# AnchorBoard_SNS_Power.net
KiCad netlist of a schematic drawn in Altium Designer
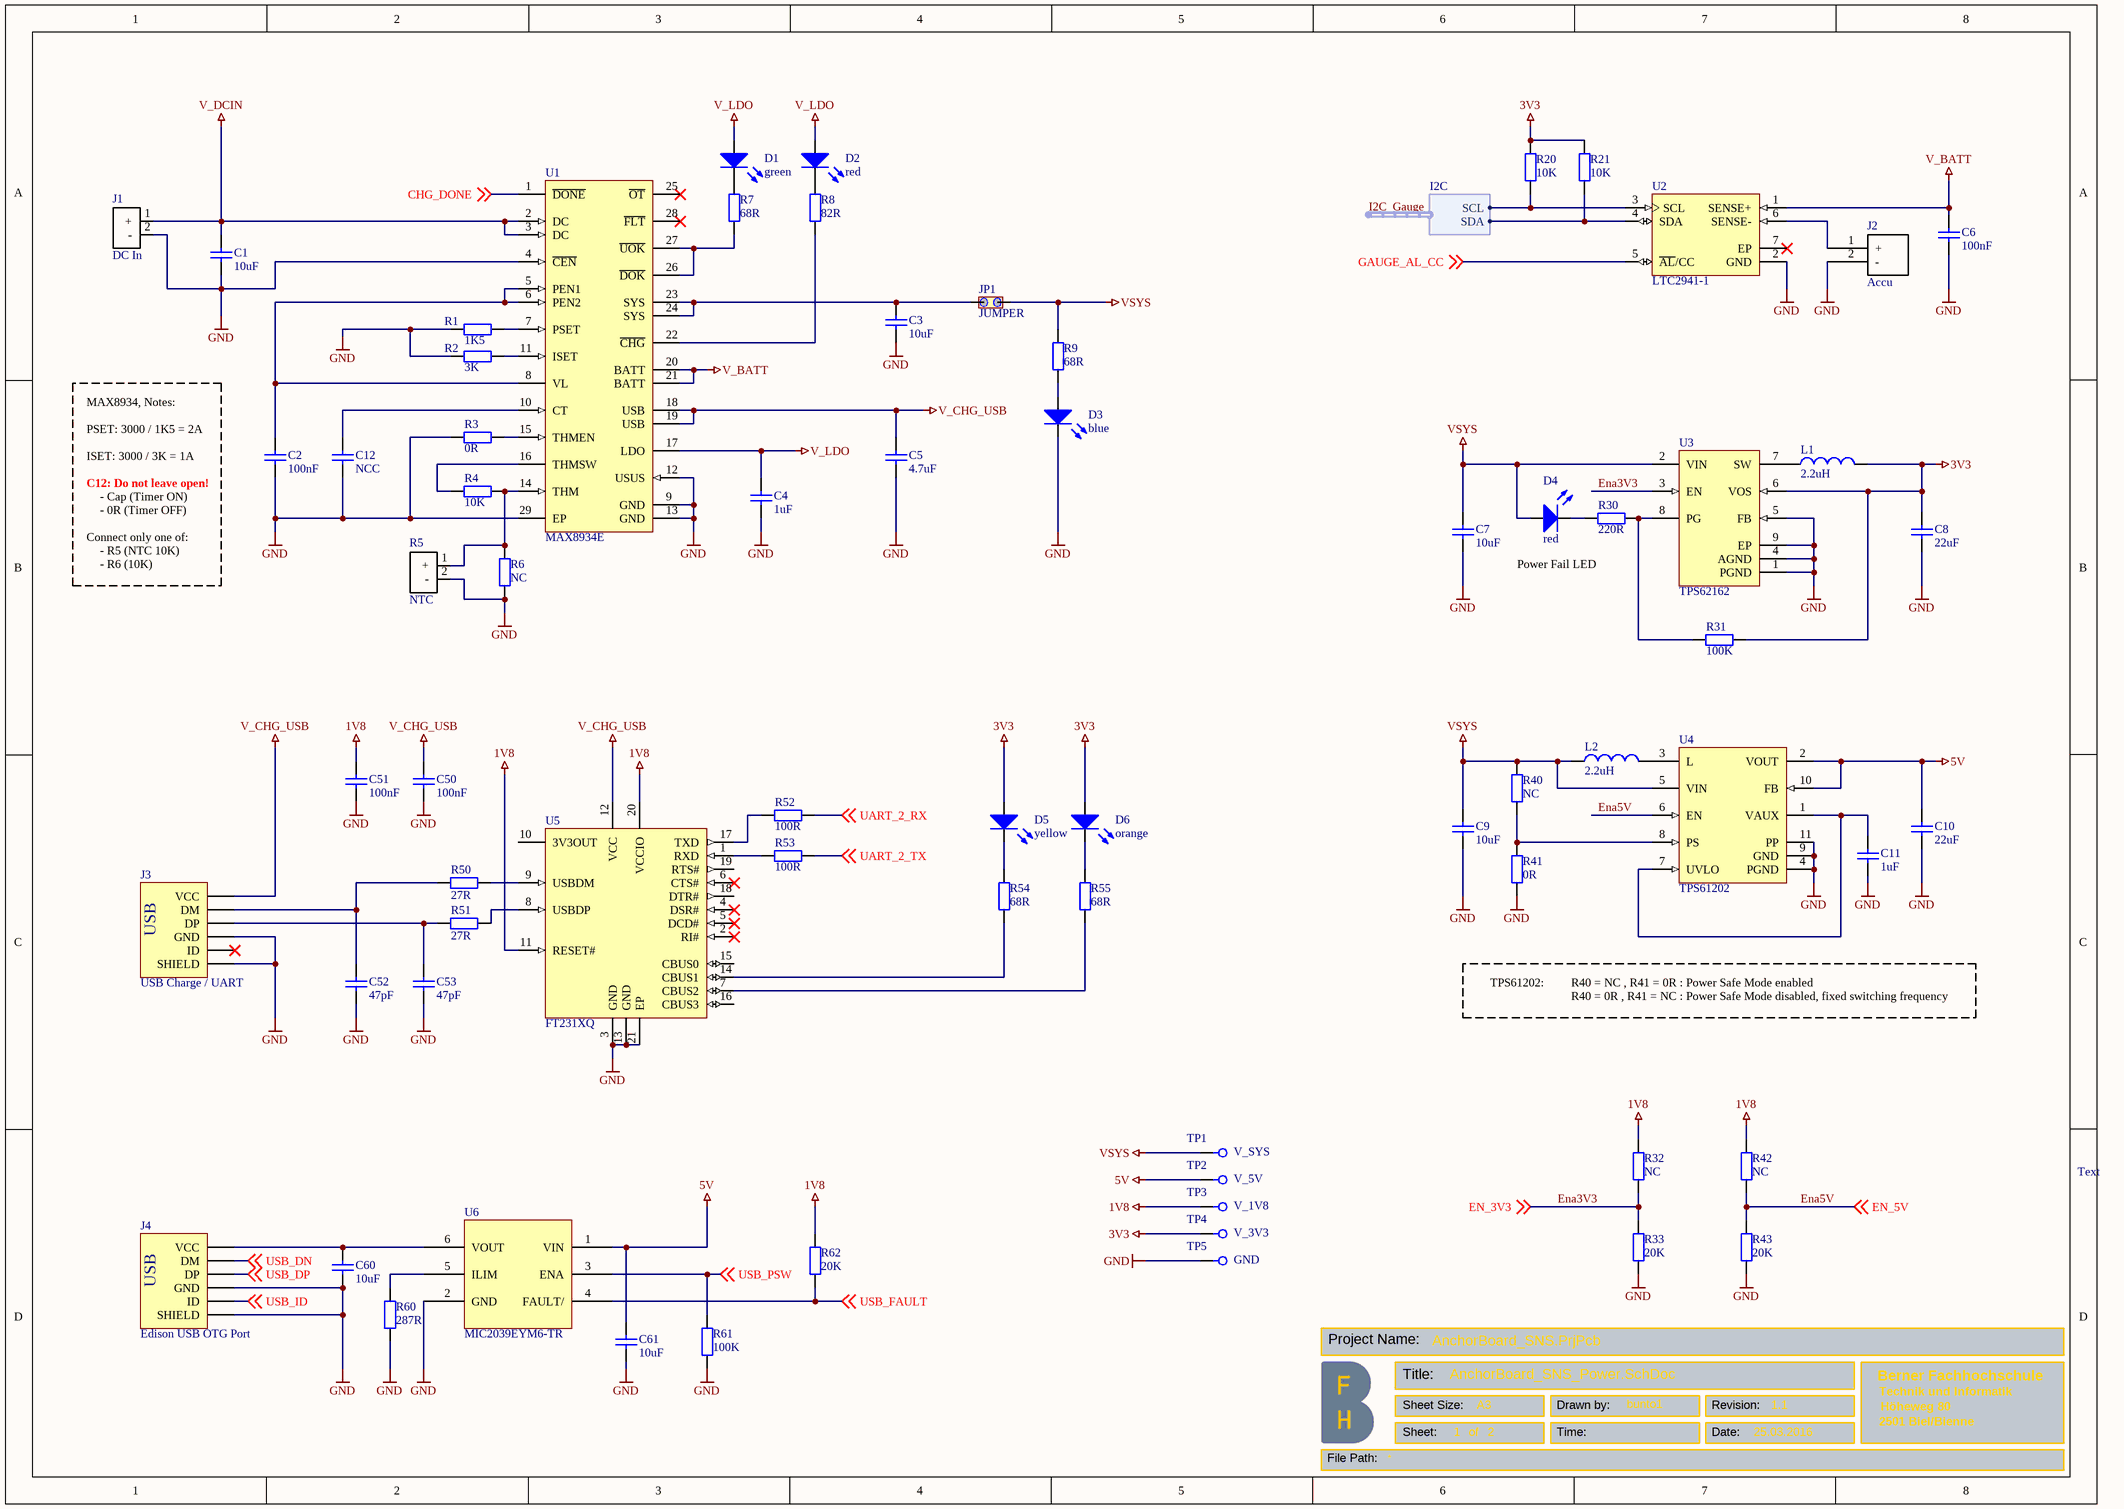
[diagram p0: AnchorBoard_SNS_Power.SchDoc]

(export (version "E")
  (design (tool "Eeschema 10.0.6"))
  (components
    (comp (ref "C1")
      (value "10uF")
      (footprint "CAPC1608X80")
      (description "Capacitor SMD Ceramic X7R")
      (libsource (lib "AnchorBoard_SNS") (part "Capacitor"))
    )
    (comp (ref "C2")
      (value "100nF")
      (footprint "CAPC1005X50")
      (description "Capacitor SMD")
      (libsource (lib "AnchorBoard_SNS") (part "Capacitor"))
    )
    (comp (ref "C3")
      (value "10uF")
      (footprint "CAPC1608X80")
      (description "Capacitor SMD Ceramic X7R")
      (libsource (lib "AnchorBoard_SNS") (part "Capacitor"))
    )
    (comp (ref "C4")
      (value "1uF")
      (footprint "CAPC1005X50")
      (description "Capacitor SMD Ceramic X7R Low ESR")
      (libsource (lib "AnchorBoard_SNS") (part "Capacitor"))
    )
    (comp (ref "C5")
      (value "4.7uF")
      (footprint "CAPC1608X80")
      (description "Capacitor SMD Ceramic X7R")
      (libsource (lib "AnchorBoard_SNS") (part "Capacitor"))
    )
    (comp (ref "C6")
      (value "100nF")
      (footprint "CAPC1005X50")
      (description "Capacitor SMD")
      (libsource (lib "AnchorBoard_SNS") (part "Capacitor"))
    )
    (comp (ref "C7")
      (value "10uF")
      (footprint "CAPC1608X80")
      (description "Capacitor SMD Ceramic X7R")
      (libsource (lib "AnchorBoard_SNS") (part "Capacitor"))
    )
    (comp (ref "C8")
      (value "22uF")
      (footprint "CAPC1608X80")
      (description "Capacitor SMD Ceramic X7R Low ESR")
      (libsource (lib "AnchorBoard_SNS") (part "Capacitor"))
    )
    (comp (ref "C9")
      (value "10uF")
      (footprint "CAPC1608X80")
      (description "Capacitor SMD Ceramic X7R")
      (libsource (lib "AnchorBoard_SNS") (part "Capacitor"))
    )
    (comp (ref "C10")
      (value "22uF")
      (footprint "CAPC1608X80")
      (description "Capacitor SMD Ceramic X7R Low ESR")
      (libsource (lib "AnchorBoard_SNS") (part "Capacitor"))
    )
    (comp (ref "C11")
      (value "1uF")
      (footprint "CAPC1005X50")
      (description "Capacitor SMD Ceramic X7R Low ESR")
      (libsource (lib "AnchorBoard_SNS") (part "Capacitor"))
    )
    (comp (ref "C12")
      (value "NCC")
      (footprint "RESC1005X35")
      (description "Capacitor SMD Ceramic X7R")
      (libsource (lib "AnchorBoard_SNS") (part "Capacitor"))
    )
    (comp (ref "C50")
      (value "100nF")
      (footprint "CAPC1005X50")
      (description "Capacitor SMD")
      (libsource (lib "AnchorBoard_SNS") (part "Capacitor"))
    )
    (comp (ref "C51")
      (value "100nF")
      (footprint "CAPC1005X50")
      (description "Capacitor SMD")
      (libsource (lib "AnchorBoard_SNS") (part "Capacitor"))
    )
    (comp (ref "C52")
      (value "47pF")
      (footprint "CAPC1005X50")
      (description "Capacitor SMD")
      (libsource (lib "AnchorBoard_SNS") (part "Capacitor"))
    )
    (comp (ref "C53")
      (value "47pF")
      (footprint "CAPC1005X50")
      (description "Capacitor SMD")
      (libsource (lib "AnchorBoard_SNS") (part "Capacitor"))
    )
    (comp (ref "C60")
      (value "10uF")
      (footprint "CAPC1608X80")
      (description "Capacitor SMD Ceramic X7R")
      (libsource (lib "AnchorBoard_SNS") (part "Capacitor"))
    )
    (comp (ref "C61")
      (value "10uF")
      (footprint "CAPC1608X80")
      (description "Capacitor SMD Ceramic X7R")
      (libsource (lib "AnchorBoard_SNS") (part "Capacitor"))
    )
    (comp (ref "D1")
      (value "green")
      (footprint "LEDM1608X80")
      (description "Light Emitting Diode")
      (fields (field (name "MANUFACTURER") "Lite-On") (field (name "MODIFIED_BY") "bunto1"))
      (libsource (lib "AnchorBoard_SNS") (part "LED_green"))
    )
    (comp (ref "D2")
      (value "red")
      (footprint "LEDM1608X80")
      (description "Light Emitting Diode")
      (fields (field (name "MANUFACTURER") "Lite-On") (field (name "MODIFIED_BY") "bunto1"))
      (libsource (lib "AnchorBoard_SNS") (part "LED_red"))
    )
    (comp (ref "D3")
      (value "blue")
      (footprint "LEDM1608X80")
      (description "Light Emitting Diode")
      (fields (field (name "MANUFACTURER") "Lite-On") (field (name "MODIFIED_BY") "bunto1"))
      (libsource (lib "AnchorBoard_SNS") (part "LED_blue"))
    )
    (comp (ref "D4")
      (value "red")
      (footprint "LEDM1608X80")
      (description "Light Emitting Diode")
      (fields (field (name "MANUFACTURER") "Lite-On") (field (name "MODIFIED_BY") "bunto1"))
      (libsource (lib "AnchorBoard_SNS") (part "LED_red"))
    )
    (comp (ref "D5")
      (value "yellow")
      (footprint "LEDM1608X80")
      (description "Light Emitting Diode")
      (fields (field (name "MANUFACTURER") "Lite-On") (field (name "MODIFIED_BY") "bunto1"))
      (libsource (lib "AnchorBoard_SNS") (part "LED_yellow"))
    )
    (comp (ref "D6")
      (value "orange")
      (footprint "LEDM1608X80")
      (description "Light Emitting Diode")
      (fields (field (name "MANUFACTURER") "Lite-On") (field (name "MODIFIED_BY") "bunto1"))
      (libsource (lib "AnchorBoard_SNS") (part "LED_orange"))
    )
    (comp (ref "J1")
      (value "DC In")
      (footprint "ACCU_PORT")
      (description "2-Pin THT Port")
      (libsource (lib "AnchorBoard_SNS") (part "PORT_THT"))
    )
    (comp (ref "J2")
      (value "Accu")
      (footprint "ACCU_PORT")
      (description "Accu Port")
      (libsource (lib "AnchorBoard_SNS") (part "ACCU_PORT"))
    )
    (comp (ref "J3")
      (value "USB Charge / UART")
      (footprint "MOLEX_0473460001")
      (description "USB Connectors MICRO USB B RECPT")
      (libsource (lib "AnchorBoard_SNS") (part "USB_micro_B"))
    )
    (comp (ref "J4")
      (value "Edison USB OTG Port")
      (footprint "MOLEX_0473460001")
      (description "USB Connectors MICRO USB B RECPT")
      (libsource (lib "AnchorBoard_SNS") (part "USB_micro_B"))
    )
    (comp (ref "JP1")
      (value "JUMPER")
      (footprint "HDR1X2_V_M")
      (description "Jumper")
      (libsource (lib "AnchorBoard_SNS") (part "JUMPER"))
    )
    (comp (ref "L1")
      (value "2.2uH")
      (footprint "INDM2929X140")
      (description "Inductor")
      (fields (field (name "MODIFIED_BY") "BEP"))
      (libsource (lib "AnchorBoard_SNS") (part "L"))
    )
    (comp (ref "L2")
      (value "2.2uH")
      (footprint "INDM2929X140")
      (description "Inductor")
      (fields (field (name "MODIFIED_BY") "BEP"))
      (libsource (lib "AnchorBoard_SNS") (part "L"))
    )
    (comp (ref "R1")
      (value "1K5")
      (footprint "RESC1005X35")
      (description "Resistor")
      (libsource (lib "") (part "Resistor_1"))
    )
    (comp (ref "R2")
      (value "3K")
      (footprint "RESC1005X35")
      (description "Resistor")
      (libsource (lib "") (part "Resistor_1"))
    )
    (comp (ref "R3")
      (value "0R")
      (footprint "RESC1005X35")
      (description "Resistor")
      (libsource (lib "") (part "Resistor_3"))
    )
    (comp (ref "R4")
      (value "10K")
      (footprint "RESC1005X35")
      (description "Resistor")
      (libsource (lib "") (part "Resistor_1"))
    )
    (comp (ref "R5")
      (value "NTC")
      (footprint "ACCU_PORT")
      (description "2-Pin THT Port")
      (libsource (lib "AnchorBoard_SNS") (part "PORT_THT"))
    )
    (comp (ref "R6")
      (value "NC")
      (footprint "RESC1005X35")
      (description "Resistor")
      (libsource (lib "AnchorBoard_SNS") (part "Resistor"))
    )
    (comp (ref "R7")
      (value "68R")
      (footprint "RESC1005X35")
      (description "Resistor")
      (libsource (lib "AnchorBoard_SNS") (part "Resistor"))
    )
    (comp (ref "R8")
      (value "82R")
      (footprint "RESC1005X35")
      (description "Resistor")
      (libsource (lib "") (part "Resistor_2"))
    )
    (comp (ref "R9")
      (value "68R")
      (footprint "RESC1005X35")
      (description "Resistor")
      (libsource (lib "AnchorBoard_SNS") (part "Resistor"))
    )
    (comp (ref "R20")
      (value "10K")
      (footprint "RESC1005X35")
      (description "Resistor")
      (libsource (lib "AnchorBoard_SNS") (part "Resistor"))
    )
    (comp (ref "R21")
      (value "10K")
      (footprint "RESC1005X35")
      (description "Resistor")
      (libsource (lib "AnchorBoard_SNS") (part "Resistor"))
    )
    (comp (ref "R30")
      (value "220R")
      (footprint "RESC1005X35")
      (description "Resistor")
      (libsource (lib "") (part "Resistor_3"))
    )
    (comp (ref "R31")
      (value "100K")
      (footprint "RESC1005X35")
      (description "Resistor")
      (libsource (lib "") (part "Resistor_3"))
    )
    (comp (ref "R32")
      (value "NC")
      (footprint "RESC1005X35")
      (description "Resistor")
      (libsource (lib "") (part "Resistor_2"))
    )
    (comp (ref "R33")
      (value "20K")
      (footprint "RESC1005X35")
      (description "Resistor")
      (libsource (lib "AnchorBoard_SNS") (part "Resistor"))
    )
    (comp (ref "R40")
      (value "NC")
      (footprint "RESC1005X35")
      (description "Resistor")
      (libsource (lib "") (part "Resistor_2"))
    )
    (comp (ref "R41")
      (value "0R")
      (footprint "RESC1005X35")
      (description "Resistor")
      (libsource (lib "") (part "Resistor_2"))
    )
    (comp (ref "R42")
      (value "NC")
      (footprint "RESC1005X35")
      (description "Resistor")
      (libsource (lib "") (part "Resistor_2"))
    )
    (comp (ref "R43")
      (value "20K")
      (footprint "RESC1005X35")
      (description "Resistor")
      (libsource (lib "AnchorBoard_SNS") (part "Resistor"))
    )
    (comp (ref "R50")
      (value "27R")
      (footprint "RESC1005X35")
      (description "Resistor")
      (libsource (lib "") (part "Resistor_3"))
    )
    (comp (ref "R51")
      (value "27R")
      (footprint "RESC1005X35")
      (description "Resistor")
      (libsource (lib "") (part "Resistor_3"))
    )
    (comp (ref "R52")
      (value "100R")
      (footprint "RESC1005X35")
      (description "Resistor")
      (libsource (lib "") (part "Resistor_1"))
    )
    (comp (ref "R53")
      (value "100R")
      (footprint "RESC1005X35")
      (description "Resistor")
      (libsource (lib "") (part "Resistor_1"))
    )
    (comp (ref "R54")
      (value "68R")
      (footprint "RESC1005X35")
      (description "Resistor")
      (libsource (lib "AnchorBoard_SNS") (part "Resistor"))
    )
    (comp (ref "R55")
      (value "68R")
      (footprint "RESC1005X35")
      (description "Resistor")
      (libsource (lib "") (part "Resistor_2"))
    )
    (comp (ref "R60")
      (value "287R")
      (footprint "RESC1005X35")
      (description "Resistor")
      (libsource (lib "AnchorBoard_SNS") (part "Resistor"))
    )
    (comp (ref "R61")
      (value "100K")
      (footprint "RESC1005X35")
      (description "Resistor")
      (libsource (lib "AnchorBoard_SNS") (part "Resistor"))
    )
    (comp (ref "R62")
      (value "20K")
      (footprint "RESC1005X35")
      (description "Resistor")
      (libsource (lib "AnchorBoard_SNS") (part "Resistor"))
    )
    (comp (ref "TP1")
      (value "V_SYS")
      (footprint "TP_THT")
      (description "Test-Point")
      (libsource (lib "AnchorBoard_SNS") (part "TP1"))
    )
    (comp (ref "TP2")
      (value "V_5V")
      (footprint "TP_THT")
      (description "Test-Point")
      (libsource (lib "AnchorBoard_SNS") (part "TP1"))
    )
    (comp (ref "TP3")
      (value "V_1V8")
      (footprint "TP_THT")
      (description "Test-Point")
      (libsource (lib "AnchorBoard_SNS") (part "TP1"))
    )
    (comp (ref "TP4")
      (value "V_3V3")
      (footprint "TP_THT")
      (description "Test-Point")
      (libsource (lib "AnchorBoard_SNS") (part "TP1"))
    )
    (comp (ref "TP5")
      (value "GND")
      (footprint "TP_THT")
      (description "Test-Point")
      (libsource (lib "AnchorBoard_SNS") (part "TP1"))
    )
    (comp (ref "U1")
      (value "MAX8934E")
      (footprint "QFN40P40X40X80-29")
      (description "IC BATTERY CHARGER DUAL 28TQFN")
      (libsource (lib "AnchorBoard_SNS") (part "MAX8934E"))
    )
    (comp (ref "U2")
      (value "LTC2941-1")
      (footprint "DFN30X20X80-6")
      (description "IC FUEL/GAS GAUGE LI-ION 1A 6DFN")
      (libsource (lib "AnchorBoard_SNS") (part "LTC2941-1"))
    )
    (comp (ref "U3")
      (value "TPS62162")
      (footprint "SON50P210X210X80-9")
      (description "IC REG BUCK 3.3V 1A SYNC 8WSON")
      (libsource (lib "AnchorBoard_SNS") (part "TPS62162"))
    )
    (comp (ref "U4")
      (value "TPS61202")
      (footprint "SON50P310X310X100-11")
      (description "IC REG BOOST 5V 1.2A SYNC 10SON")
      (libsource (lib "AnchorBoard_SNS") (part "TPS61202"))
    )
    (comp (ref "U5")
      (value "FT231XQ")
      (footprint "QFN50P40X40X80-21")
      (description "IC USB SERIAL FULL UART 20QFN")
      (libsource (lib "AnchorBoard_SNS") (part "FT231XQ"))
    )
    (comp (ref "U6")
      (value "MIC2039EYM6-TR")
      (footprint "SOT95P360X130-6")
      (description "Adjustable Current Limit Power Switch")
      (libsource (lib "AnchorBoard_SNS") (part "MIC2039"))
    )
  )
  (nets
    (net (code "3") (name "1V8") (class "Default")
      (node (ref "C51") (pin "2") (pinfunction "2_2") (pintype "passive"))
      (node (ref "R32") (pin "2") (pinfunction "2_2") (pintype "passive"))
      (node (ref "R42") (pin "2") (pinfunction "2_2") (pintype "passive"))
      (node (ref "R62") (pin "1") (pinfunction "1_1") (pintype "passive"))
      (node (ref "TP3") (pin "1") (pinfunction "TP_1") (pintype "passive"))
      (node (ref "U5") (pin "11") (pinfunction "RESET#_11") (pintype "input"))
      (node (ref "U5") (pin "20") (pinfunction "VCCIO_20") (pintype "power_in"))
    )
    (net (code "4") (name "3V3") (class "Default")
      (node (ref "C8") (pin "2") (pinfunction "2_2") (pintype "passive"))
      (node (ref "D5") (pin "1") (pinfunction "A_1") (pintype "passive"))
      (node (ref "D6") (pin "1") (pinfunction "A_1") (pintype "passive"))
      (node (ref "L1") (pin "2") (pintype "passive"))
      (node (ref "R20") (pin "1") (pinfunction "1_1") (pintype "passive"))
      (node (ref "R21") (pin "1") (pinfunction "1_1") (pintype "passive"))
      (node (ref "R31") (pin "2") (pinfunction "2_2") (pintype "passive"))
      (node (ref "TP4") (pin "1") (pinfunction "TP_1") (pintype "passive"))
      (node (ref "U3") (pin "6") (pinfunction "VOS_6") (pintype "input"))
    )
    (net (code "5") (name "5V") (class "Default")
      (node (ref "C10") (pin "2") (pinfunction "2_2") (pintype "passive"))
      (node (ref "C61") (pin "2") (pinfunction "2_2") (pintype "passive"))
      (node (ref "TP2") (pin "1") (pinfunction "TP_1") (pintype "passive"))
      (node (ref "U4") (pin "10") (pinfunction "FB_10") (pintype "input"))
      (node (ref "U4") (pin "2") (pinfunction "VOUT_2") (pintype "power_in"))
      (node (ref "U6") (pin "1") (pinfunction "VIN_1") (pintype "passive"))
    )
    (net (code "6") (name "CHG_DONE") (class "Default")
      (node (ref "U1") (pin "1") (pinfunction "~{DONE}_1") (pintype "passive"))
    )
    (net (code "7") (name "EN_3V3") (class "Default")
      (node (ref "R32") (pin "1") (pinfunction "1_1") (pintype "passive"))
      (node (ref "R33") (pin "1") (pinfunction "1_1") (pintype "passive"))
      (node (ref "U3") (pin "3") (pinfunction "EN_3") (pintype "input"))
    )
    (net (code "8") (name "EN_5V") (class "Default")
      (node (ref "R42") (pin "1") (pinfunction "1_1") (pintype "passive"))
      (node (ref "R43") (pin "1") (pinfunction "1_1") (pintype "passive"))
      (node (ref "U4") (pin "6") (pinfunction "EN_6") (pintype "input"))
    )
    (net (code "9") (name "GAUGE_AL_CC") (class "Default")
      (node (ref "U2") (pin "5") (pinfunction "~{AL}/CC_5") (pintype "bidirectional"))
    )
    (net (code "10") (name "GND") (class "Default")
      (node (ref "C1") (pin "1") (pinfunction "1_1") (pintype "passive"))
      (node (ref "C10") (pin "1") (pinfunction "1_1") (pintype "passive"))
      (node (ref "C11") (pin "1") (pinfunction "1_1") (pintype "passive"))
      (node (ref "C12") (pin "1") (pinfunction "1_1") (pintype "passive"))
      (node (ref "C2") (pin "1") (pinfunction "1_1") (pintype "passive"))
      (node (ref "C3") (pin "1") (pinfunction "1_1") (pintype "passive"))
      (node (ref "C4") (pin "1") (pinfunction "1_1") (pintype "passive"))
      (node (ref "C5") (pin "1") (pinfunction "1_1") (pintype "passive"))
      (node (ref "C50") (pin "1") (pinfunction "1_1") (pintype "passive"))
      (node (ref "C51") (pin "1") (pinfunction "1_1") (pintype "passive"))
      (node (ref "C52") (pin "1") (pinfunction "1_1") (pintype "passive"))
      (node (ref "C53") (pin "1") (pinfunction "1_1") (pintype "passive"))
      (node (ref "C6") (pin "1") (pinfunction "1_1") (pintype "passive"))
      (node (ref "C60") (pin "1") (pinfunction "1_1") (pintype "passive"))
      (node (ref "C61") (pin "1") (pinfunction "1_1") (pintype "passive"))
      (node (ref "C7") (pin "1") (pinfunction "1_1") (pintype "passive"))
      (node (ref "C8") (pin "1") (pinfunction "1_1") (pintype "passive"))
      (node (ref "C9") (pin "1") (pinfunction "1_1") (pintype "passive"))
      (node (ref "D3") (pin "2") (pinfunction "K_2") (pintype "passive"))
      (node (ref "J1") (pin "2") (pinfunction "-_2") (pintype "passive"))
      (node (ref "J2") (pin "2") (pinfunction "-_2") (pintype "passive"))
      (node (ref "J3") (pin "5") (pinfunction "GND_5") (pintype "passive"))
      (node (ref "J3") (pin "6") (pinfunction "SHIELD_6") (pintype "passive"))
      (node (ref "J4") (pin "5") (pinfunction "GND_5") (pintype "passive"))
      (node (ref "J4") (pin "6") (pinfunction "SHIELD_6") (pintype "passive"))
      (node (ref "R1") (pin "2") (pinfunction "2_2") (pintype "passive"))
      (node (ref "R2") (pin "2") (pinfunction "2_2") (pintype "passive"))
      (node (ref "R3") (pin "1") (pinfunction "1_1") (pintype "passive"))
      (node (ref "R33") (pin "2") (pinfunction "2_2") (pintype "passive"))
      (node (ref "R41") (pin "1") (pinfunction "1_1") (pintype "passive"))
      (node (ref "R43") (pin "2") (pinfunction "2_2") (pintype "passive"))
      (node (ref "R5") (pin "2") (pinfunction "-_2") (pintype "passive"))
      (node (ref "R6") (pin "2") (pinfunction "2_2") (pintype "passive"))
      (node (ref "R60") (pin "2") (pinfunction "2_2") (pintype "passive"))
      (node (ref "R61") (pin "2") (pinfunction "2_2") (pintype "passive"))
      (node (ref "TP5") (pin "1") (pinfunction "TP_1") (pintype "passive"))
      (node (ref "U1") (pin "12") (pinfunction "USUS_12") (pintype "input"))
      (node (ref "U1") (pin "13") (pinfunction "GND_13") (pintype "power_in"))
      (node (ref "U1") (pin "29") (pinfunction "EP_29") (pintype "power_in"))
      (node (ref "U1") (pin "4") (pinfunction "~{CEN}_4") (pintype "input"))
      (node (ref "U1") (pin "9") (pinfunction "GND_9") (pintype "power_in"))
      (node (ref "U2") (pin "2") (pinfunction "GND_2") (pintype "power_in"))
      (node (ref "U3") (pin "1") (pinfunction "PGND_1") (pintype "power_in"))
      (node (ref "U3") (pin "4") (pinfunction "AGND_4") (pintype "power_in"))
      (node (ref "U3") (pin "5") (pinfunction "FB_5") (pintype "input"))
      (node (ref "U3") (pin "9") (pinfunction "EP_9") (pintype "power_in"))
      (node (ref "U4") (pin "11") (pinfunction "PP_11") (pintype "power_in"))
      (node (ref "U4") (pin "4") (pinfunction "PGND_4") (pintype "power_in"))
      (node (ref "U4") (pin "9") (pinfunction "GND_9") (pintype "power_in"))
      (node (ref "U5") (pin "13") (pinfunction "GND_13") (pintype "power_in"))
      (node (ref "U5") (pin "21") (pinfunction "EP_21") (pintype "power_in"))
      (node (ref "U5") (pin "3") (pinfunction "GND_3") (pintype "power_in"))
      (node (ref "U6") (pin "2") (pinfunction "GND_2") (pintype "passive"))
    )
    (net (code "11") (name "Net-(C3-Pad2)") (class "Default")
      (node (ref "C3") (pin "2") (pinfunction "2_2") (pintype "passive"))
      (node (ref "JP1") (pin "1") (pintype "passive"))
      (node (ref "U1") (pin "23") (pinfunction "SYS_23") (pintype "power_in"))
      (node (ref "U1") (pin "24") (pinfunction "SYS_24") (pintype "power_in"))
    )
    (net (code "12") (name "Net-(D1-K)") (class "Default")
      (node (ref "D1") (pin "2") (pinfunction "K_2") (pintype "passive"))
      (node (ref "R7") (pin "1") (pinfunction "1_1") (pintype "passive"))
    )
    (net (code "13") (name "Net-(D2-K)") (class "Default")
      (node (ref "D2") (pin "2") (pinfunction "K_2") (pintype "passive"))
      (node (ref "R8") (pin "2") (pinfunction "2_2") (pintype "passive"))
    )
    (net (code "14") (name "Net-(D3-A)") (class "Default")
      (node (ref "D3") (pin "1") (pinfunction "A_1") (pintype "passive"))
      (node (ref "R9") (pin "2") (pinfunction "2_2") (pintype "passive"))
    )
    (net (code "15") (name "Net-(D4-K)") (class "Default")
      (node (ref "D4") (pin "2") (pinfunction "K_2") (pintype "passive"))
      (node (ref "R30") (pin "1") (pinfunction "1_1") (pintype "passive"))
    )
    (net (code "16") (name "Net-(D5-K)") (class "Default")
      (node (ref "D5") (pin "2") (pinfunction "K_2") (pintype "passive"))
      (node (ref "R54") (pin "1") (pinfunction "1_1") (pintype "passive"))
    )
    (net (code "17") (name "Net-(D6-K)") (class "Default")
      (node (ref "D6") (pin "2") (pinfunction "K_2") (pintype "passive"))
      (node (ref "R55") (pin "2") (pinfunction "2_2") (pintype "passive"))
    )
    (net (code "18") (name "Net-(J2-+)") (class "Default")
      (node (ref "J2") (pin "1") (pinfunction "+_1") (pintype "passive"))
      (node (ref "U2") (pin "6") (pinfunction "SENSE-_6") (pintype "input"))
    )
    (net (code "19") (name "Net-(J3-DM)") (class "Default")
      (node (ref "C52") (pin "2") (pinfunction "2_2") (pintype "passive"))
      (node (ref "J3") (pin "2") (pinfunction "DM_2") (pintype "passive"))
      (node (ref "R50") (pin "1") (pinfunction "1_1") (pintype "passive"))
    )
    (net (code "20") (name "Net-(J3-DP)") (class "Default")
      (node (ref "C53") (pin "2") (pinfunction "2_2") (pintype "passive"))
      (node (ref "J3") (pin "3") (pinfunction "DP_3") (pintype "passive"))
      (node (ref "R51") (pin "1") (pinfunction "1_1") (pintype "passive"))
    )
    (net (code "21") (name "Net-(J4-VCC)") (class "Default")
      (node (ref "C60") (pin "2") (pinfunction "2_2") (pintype "passive"))
      (node (ref "J4") (pin "1") (pinfunction "VCC_1") (pintype "passive"))
      (node (ref "U6") (pin "6") (pinfunction "VOUT_6") (pintype "passive"))
    )
    (net (code "22") (name "Net-(R5-+)") (class "Default")
      (node (ref "R4") (pin "1") (pinfunction "1_1") (pintype "passive"))
      (node (ref "R5") (pin "1") (pinfunction "+_1") (pintype "passive"))
      (node (ref "R6") (pin "1") (pinfunction "1_1") (pintype "passive"))
      (node (ref "U1") (pin "14") (pinfunction "THM_14") (pintype "input"))
    )
    (net (code "23") (name "Net-(U1-CT)") (class "Default")
      (node (ref "C12") (pin "2") (pinfunction "2_2") (pintype "passive"))
      (node (ref "U1") (pin "10") (pinfunction "CT_10") (pintype "input"))
    )
    (net (code "24") (name "Net-(U1-ISET)") (class "Default")
      (node (ref "R2") (pin "1") (pinfunction "1_1") (pintype "passive"))
      (node (ref "U1") (pin "11") (pinfunction "ISET_11") (pintype "input"))
    )
    (net (code "25") (name "Net-(U1-PEN1)") (class "Default")
      (node (ref "C2") (pin "2") (pinfunction "2_2") (pintype "passive"))
      (node (ref "U1") (pin "5") (pinfunction "PEN1_5") (pintype "input"))
      (node (ref "U1") (pin "6") (pinfunction "PEN2_6") (pintype "input"))
      (node (ref "U1") (pin "8") (pinfunction "VL_8") (pintype "power_in"))
    )
    (net (code "26") (name "Net-(U1-PSET)") (class "Default")
      (node (ref "R1") (pin "1") (pinfunction "1_1") (pintype "passive"))
      (node (ref "U1") (pin "7") (pinfunction "PSET_7") (pintype "input"))
    )
    (net (code "27") (name "Net-(U1-THMEN)") (class "Default")
      (node (ref "R3") (pin "2") (pinfunction "2_2") (pintype "passive"))
      (node (ref "U1") (pin "15") (pinfunction "THMEN_15") (pintype "input"))
    )
    (net (code "28") (name "Net-(U1-THMSW)") (class "Default")
      (node (ref "R4") (pin "2") (pinfunction "2_2") (pintype "passive"))
      (node (ref "U1") (pin "16") (pinfunction "THMSW_16") (pintype "passive"))
    )
    (net (code "29") (name "Net-(U1-~{CHG})") (class "Default")
      (node (ref "R8") (pin "1") (pinfunction "1_1") (pintype "passive"))
      (node (ref "U1") (pin "22") (pinfunction "~{CHG}_22") (pintype "passive"))
    )
    (net (code "30") (name "Net-(U1-~{DOK})") (class "Default")
      (node (ref "R7") (pin "2") (pinfunction "2_2") (pintype "passive"))
      (node (ref "U1") (pin "26") (pinfunction "~{DOK}_26") (pintype "open_collector"))
      (node (ref "U1") (pin "27") (pinfunction "~{UOK}_27") (pintype "open_collector"))
    )
    (net (code "31") (name "Net-(U2-SCL)") (class "Default")
      (node (ref "R20") (pin "2") (pinfunction "2_2") (pintype "passive"))
      (node (ref "U2") (pin "3") (pinfunction "SCL_3") (pintype "input"))
    )
    (net (code "32") (name "Net-(U2-SDA)") (class "Default")
      (node (ref "R21") (pin "2") (pinfunction "2_2") (pintype "passive"))
      (node (ref "U2") (pin "4") (pinfunction "SDA_4") (pintype "bidirectional"))
    )
    (net (code "33") (name "Net-(U3-PG)") (class "Default")
      (node (ref "R30") (pin "2") (pinfunction "2_2") (pintype "passive"))
      (node (ref "R31") (pin "1") (pinfunction "1_1") (pintype "passive"))
      (node (ref "U3") (pin "8") (pinfunction "PG_8") (pintype "tri_state"))
    )
    (net (code "34") (name "Net-(U3-SW)") (class "Default")
      (node (ref "L1") (pin "1") (pintype "passive"))
      (node (ref "U3") (pin "7") (pinfunction "SW_7") (pintype "power_in"))
    )
    (net (code "35") (name "Net-(U4-L)") (class "Default")
      (node (ref "L2") (pin "2") (pintype "passive"))
      (node (ref "U4") (pin "3") (pinfunction "L_3") (pintype "power_in"))
    )
    (net (code "36") (name "Net-(U4-PS)") (class "Default")
      (node (ref "R40") (pin "1") (pinfunction "1_1") (pintype "passive"))
      (node (ref "R41") (pin "2") (pinfunction "2_2") (pintype "passive"))
      (node (ref "U4") (pin "8") (pinfunction "PS_8") (pintype "input"))
    )
    (net (code "37") (name "Net-(U4-UVLO)") (class "Default")
      (node (ref "C11") (pin "2") (pinfunction "2_2") (pintype "passive"))
      (node (ref "U4") (pin "1") (pinfunction "VAUX_1") (pintype "power_in"))
      (node (ref "U4") (pin "7") (pinfunction "UVLO_7") (pintype "input"))
    )
    (net (code "38") (name "Net-(U5-CBUS1)") (class "Default")
      (node (ref "R54") (pin "2") (pinfunction "2_2") (pintype "passive"))
      (node (ref "U5") (pin "14") (pinfunction "CBUS1_14") (pintype "bidirectional"))
    )
    (net (code "39") (name "Net-(U5-CBUS2)") (class "Default")
      (node (ref "R55") (pin "1") (pinfunction "1_1") (pintype "passive"))
      (node (ref "U5") (pin "7") (pinfunction "CBUS2_7") (pintype "bidirectional"))
    )
    (net (code "40") (name "Net-(U5-RXD)") (class "Default")
      (node (ref "R53") (pin "2") (pinfunction "2_2") (pintype "passive"))
      (node (ref "U5") (pin "1") (pinfunction "RXD_1") (pintype "input"))
    )
    (net (code "41") (name "Net-(U5-TXD)") (class "Default")
      (node (ref "R52") (pin "2") (pinfunction "2_2") (pintype "passive"))
      (node (ref "U5") (pin "17") (pinfunction "TXD_17") (pintype "output"))
    )
    (net (code "42") (name "Net-(U5-USBDM)") (class "Default")
      (node (ref "R50") (pin "2") (pinfunction "2_2") (pintype "passive"))
      (node (ref "U5") (pin "9") (pinfunction "USBDM_9") (pintype "input"))
    )
    (net (code "43") (name "Net-(U5-USBDP)") (class "Default")
      (node (ref "R51") (pin "2") (pinfunction "2_2") (pintype "passive"))
      (node (ref "U5") (pin "8") (pinfunction "USBDP_8") (pintype "input"))
    )
    (net (code "44") (name "Net-(U6-ILIM)") (class "Default")
      (node (ref "R60") (pin "1") (pinfunction "1_1") (pintype "passive"))
      (node (ref "U6") (pin "5") (pinfunction "ILIM_5") (pintype "passive"))
    )
    (net (code "45") (name "UART_2_RX") (class "Default")
      (node (ref "R52") (pin "1") (pinfunction "1_1") (pintype "passive"))
    )
    (net (code "46") (name "UART_2_TX") (class "Default")
      (node (ref "R53") (pin "1") (pinfunction "1_1") (pintype "passive"))
    )
    (net (code "47") (name "USB_DN") (class "Default")
      (node (ref "J4") (pin "2") (pinfunction "DM_2") (pintype "passive"))
    )
    (net (code "48") (name "USB_DP") (class "Default")
      (node (ref "J4") (pin "3") (pinfunction "DP_3") (pintype "passive"))
    )
    (net (code "49") (name "USB_FAULT") (class "Default")
      (node (ref "R62") (pin "2") (pinfunction "2_2") (pintype "passive"))
      (node (ref "U6") (pin "4") (pinfunction "FAULT/_4") (pintype "passive"))
    )
    (net (code "50") (name "USB_ID") (class "Default")
      (node (ref "J4") (pin "4") (pinfunction "ID_4") (pintype "passive"))
    )
    (net (code "51") (name "USB_PSW") (class "Default")
      (node (ref "R61") (pin "1") (pinfunction "1_1") (pintype "passive"))
      (node (ref "U6") (pin "3") (pinfunction "ENA_3") (pintype "passive"))
    )
    (net (code "52") (name "VSYS") (class "Default")
      (node (ref "C7") (pin "2") (pinfunction "2_2") (pintype "passive"))
      (node (ref "C9") (pin "2") (pinfunction "2_2") (pintype "passive"))
      (node (ref "D4") (pin "1") (pinfunction "A_1") (pintype "passive"))
      (node (ref "JP1") (pin "2") (pintype "passive"))
      (node (ref "L2") (pin "1") (pintype "passive"))
      (node (ref "R40") (pin "2") (pinfunction "2_2") (pintype "passive"))
      (node (ref "R9") (pin "1") (pinfunction "1_1") (pintype "passive"))
      (node (ref "TP1") (pin "1") (pinfunction "TP_1") (pintype "passive"))
      (node (ref "U3") (pin "2") (pinfunction "VIN_2") (pintype "power_in"))
      (node (ref "U4") (pin "5") (pinfunction "VIN_5") (pintype "power_in"))
    )
    (net (code "53") (name "V_BATT") (class "Default")
      (node (ref "C6") (pin "2") (pinfunction "2_2") (pintype "passive"))
      (node (ref "U1") (pin "20") (pinfunction "BATT_20") (pintype "power_in"))
      (node (ref "U1") (pin "21") (pinfunction "BATT_21") (pintype "power_in"))
      (node (ref "U2") (pin "1") (pinfunction "SENSE+_1") (pintype "input"))
    )
    (net (code "54") (name "V_CHG_USB") (class "Default")
      (node (ref "C5") (pin "2") (pinfunction "2_2") (pintype "passive"))
      (node (ref "C50") (pin "2") (pinfunction "2_2") (pintype "passive"))
      (node (ref "J3") (pin "1") (pinfunction "VCC_1") (pintype "passive"))
      (node (ref "U1") (pin "18") (pinfunction "USB_18") (pintype "power_in"))
      (node (ref "U1") (pin "19") (pinfunction "USB_19") (pintype "power_in"))
      (node (ref "U5") (pin "12") (pinfunction "VCC_12") (pintype "power_in"))
    )
    (net (code "55") (name "V_DCIN") (class "Default")
      (node (ref "C1") (pin "2") (pinfunction "2_2") (pintype "passive"))
      (node (ref "J1") (pin "1") (pinfunction "+_1") (pintype "passive"))
      (node (ref "U1") (pin "2") (pinfunction "DC_2") (pintype "input"))
      (node (ref "U1") (pin "3") (pinfunction "DC_3") (pintype "input"))
    )
    (net (code "56") (name "V_LDO") (class "Default")
      (node (ref "C4") (pin "2") (pinfunction "2_2") (pintype "passive"))
      (node (ref "D1") (pin "1") (pinfunction "A_1") (pintype "passive"))
      (node (ref "D2") (pin "1") (pinfunction "A_1") (pintype "passive"))
      (node (ref "U1") (pin "17") (pinfunction "LDO_17") (pintype "power_in"))
    )
    (net (code "57") (name "unconnected-(J3-ID-Pad4)") (class "Default")
      (node (ref "J3") (pin "4") (pinfunction "ID_4") (pintype "passive+no_connect"))
    )
    (net (code "58") (name "unconnected-(U1-~{FLT}-Pad28)") (class "Default")
      (node (ref "U1") (pin "28") (pinfunction "~{FLT}_28") (pintype "open_collector+no_connect"))
    )
    (net (code "59") (name "unconnected-(U1-~{OT}-Pad25)") (class "Default")
      (node (ref "U1") (pin "25") (pinfunction "~{OT}_25") (pintype "open_collector+no_connect"))
    )
    (net (code "60") (name "unconnected-(U2-EP-Pad7)") (class "Default")
      (node (ref "U2") (pin "7") (pinfunction "EP_7") (pintype "passive+no_connect"))
    )
    (net (code "61") (name "unconnected-(U5-3V3OUT-Pad10)") (class "Default")
      (node (ref "U5") (pin "10") (pinfunction "3V3OUT_10") (pintype "power_in"))
    )
    (net (code "62") (name "unconnected-(U5-CBUS0-Pad15)") (class "Default")
      (node (ref "U5") (pin "15") (pinfunction "CBUS0_15") (pintype "bidirectional"))
    )
    (net (code "63") (name "unconnected-(U5-CBUS3-Pad16)") (class "Default")
      (node (ref "U5") (pin "16") (pinfunction "CBUS3_16") (pintype "bidirectional"))
    )
    (net (code "64") (name "unconnected-(U5-CTS#-Pad6)") (class "Default")
      (node (ref "U5") (pin "6") (pinfunction "CTS#_6") (pintype "input+no_connect"))
    )
    (net (code "65") (name "unconnected-(U5-DCD#-Pad5)") (class "Default")
      (node (ref "U5") (pin "5") (pinfunction "DCD#_5") (pintype "input+no_connect"))
    )
    (net (code "66") (name "unconnected-(U5-DSR#-Pad4)") (class "Default")
      (node (ref "U5") (pin "4") (pinfunction "DSR#_4") (pintype "input+no_connect"))
    )
    (net (code "67") (name "unconnected-(U5-DTR#-Pad18)") (class "Default")
      (node (ref "U5") (pin "18") (pinfunction "DTR#_18") (pintype "output"))
    )
    (net (code "68") (name "unconnected-(U5-RI#-Pad2)") (class "Default")
      (node (ref "U5") (pin "2") (pinfunction "RI#_2") (pintype "input+no_connect"))
    )
    (net (code "69") (name "unconnected-(U5-RTS#-Pad19)") (class "Default")
      (node (ref "U5") (pin "19") (pinfunction "RTS#_19") (pintype "output"))
    )
  )
)
